# LEDLightSticks_V2--01--Brain_Board_PCB_v.net
KiCad netlist of a schematic drawn in EAGLE
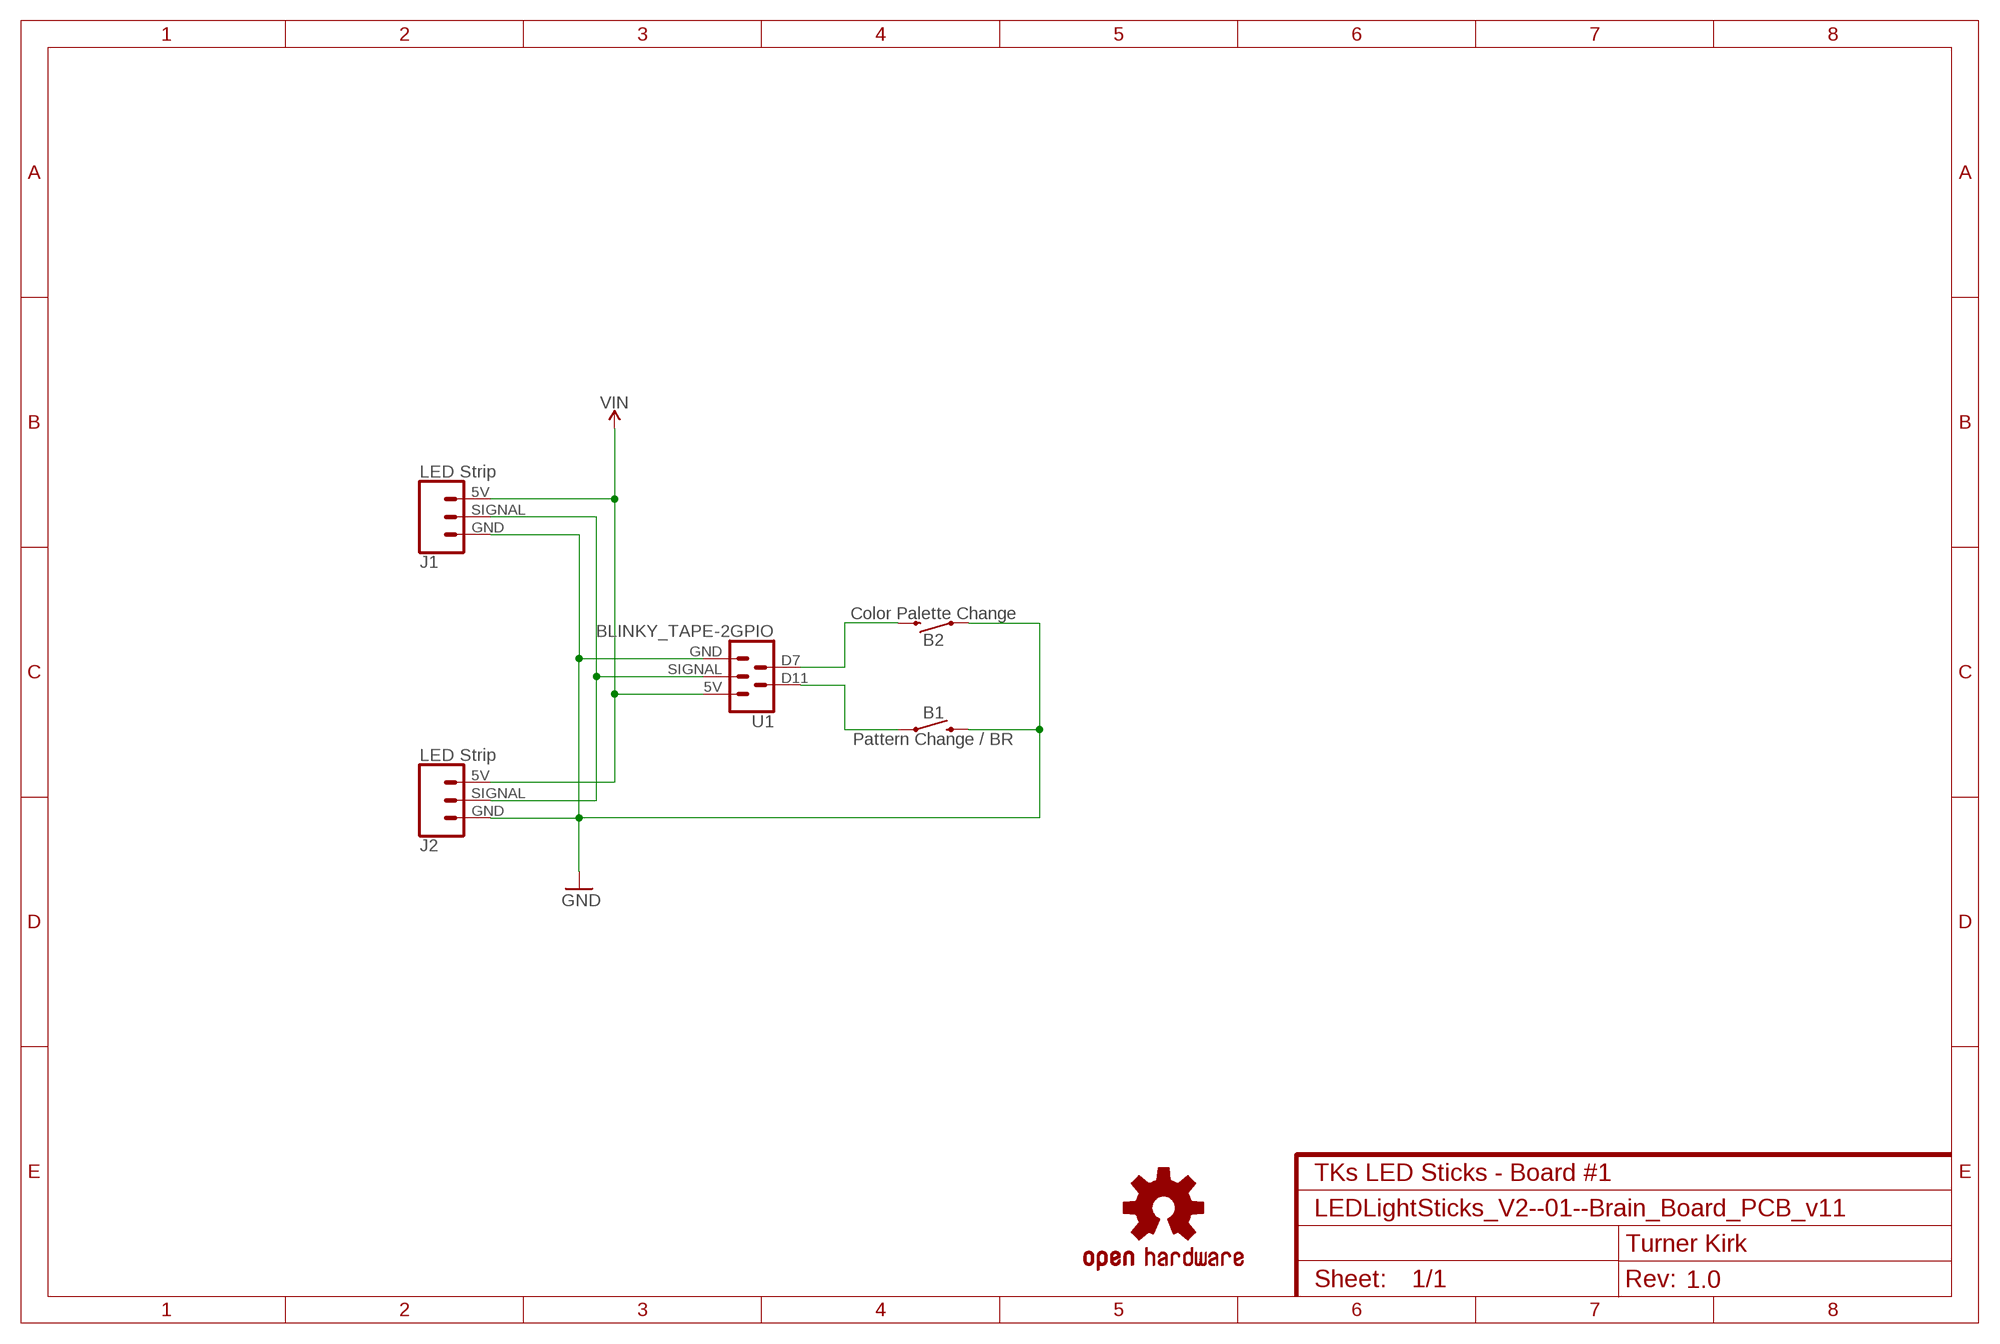
[diagram p0: schematic, sheet 1]

(export (version "E")
  (design (tool "Eeschema 10.0.6"))
  (components
    (comp (ref "B1")
      (value "Pattern Change / BR")
      (footprint "eagle-import:TACTILE_SWITCH_PTH_12MM")
      (libsource (lib "eagle-import") (part "MOMENTARY-SWITCH-SPST-PTH-12MM"))
    )
    (comp (ref "B2")
      (value "Color Palette Change")
      (footprint "eagle-import:TACTILE_SWITCH_PTH_12MM")
      (libsource (lib "eagle-import") (part "MOMENTARY-SWITCH-SPST-PTH-12MM"))
    )
    (comp (ref "J1")
      (value "LED Strip")
      (footprint "eagle-import:JST-3-PTH-XH-RA")
      (libsource (lib "eagle-import") (part "CONN_03JST-2.5-PTH-RA"))
    )
    (comp (ref "J2")
      (value "LED Strip")
      (footprint "eagle-import:JST-3-PTH-XH-RA")
      (libsource (lib "eagle-import") (part "CONN_03JST-2.5-PTH-RA"))
    )
    (comp (ref "LOGO1")
      (value "OSHW-LOGOM")
      (footprint "eagle-import:OSHW-LOGO-M")
      (libsource (lib "eagle-import") (part "OSHW-LOGOM"))
    )
    (comp (ref "U1")
      (value "BLINKY_TAPE-2GPIO")
      (footprint "eagle-import:BLINKY_TAPE-2GPIO")
      (libsource (lib "eagle-import") (part "BLINKY_TAPE-2GPIO"))
    )
  )
  (nets
    (net (code "1") (name "GND") (class "Default")
      (node (ref "B1") (pin "3") (pinfunction "2_3") (pintype "passive"))
      (node (ref "B2") (pin "1") (pinfunction "1_1") (pintype "passive"))
      (node (ref "J1") (pin "GND") (pinfunction "3_GND") (pintype "passive"))
      (node (ref "J2") (pin "GND") (pinfunction "3_GND") (pintype "passive"))
      (node (ref "U1") (pin "GND") (pinfunction "GND_GND") (pintype "power_in"))
    )
    (net (code "2") (name "Net-(B1-Pad1)") (class "Default")
      (node (ref "B1") (pin "1") (pinfunction "1_1") (pintype "passive"))
      (node (ref "U1") (pin "D11") (pinfunction "D11_D11") (pintype "bidirectional"))
    )
    (net (code "3") (name "Net-(B2-2)") (class "Default")
      (node (ref "B2") (pin "3") (pinfunction "2_3") (pintype "passive"))
      (node (ref "U1") (pin "D7") (pinfunction "D7_D7") (pintype "bidirectional"))
    )
    (net (code "4") (name "Net-(J1-2)") (class "Default")
      (node (ref "J1") (pin "SIGNAL") (pinfunction "2_SIGNAL") (pintype "passive"))
      (node (ref "J2") (pin "SIGNAL") (pinfunction "2_SIGNAL") (pintype "passive"))
      (node (ref "U1") (pin "SIGNAL") (pinfunction "SIGNAL_SIGNAL") (pintype "bidirectional"))
    )
    (net (code "5") (name "VIN") (class "Default")
      (node (ref "J1") (pin "5V") (pinfunction "1_5V") (pintype "passive"))
      (node (ref "J2") (pin "5V") (pinfunction "1_5V") (pintype "passive"))
      (node (ref "U1") (pin "5V") (pinfunction "5V_5V") (pintype "power_in"))
    )
  )
)
